# PowerManagementMysensors.net
KiCad netlist of a schematic drawn in EAGLE
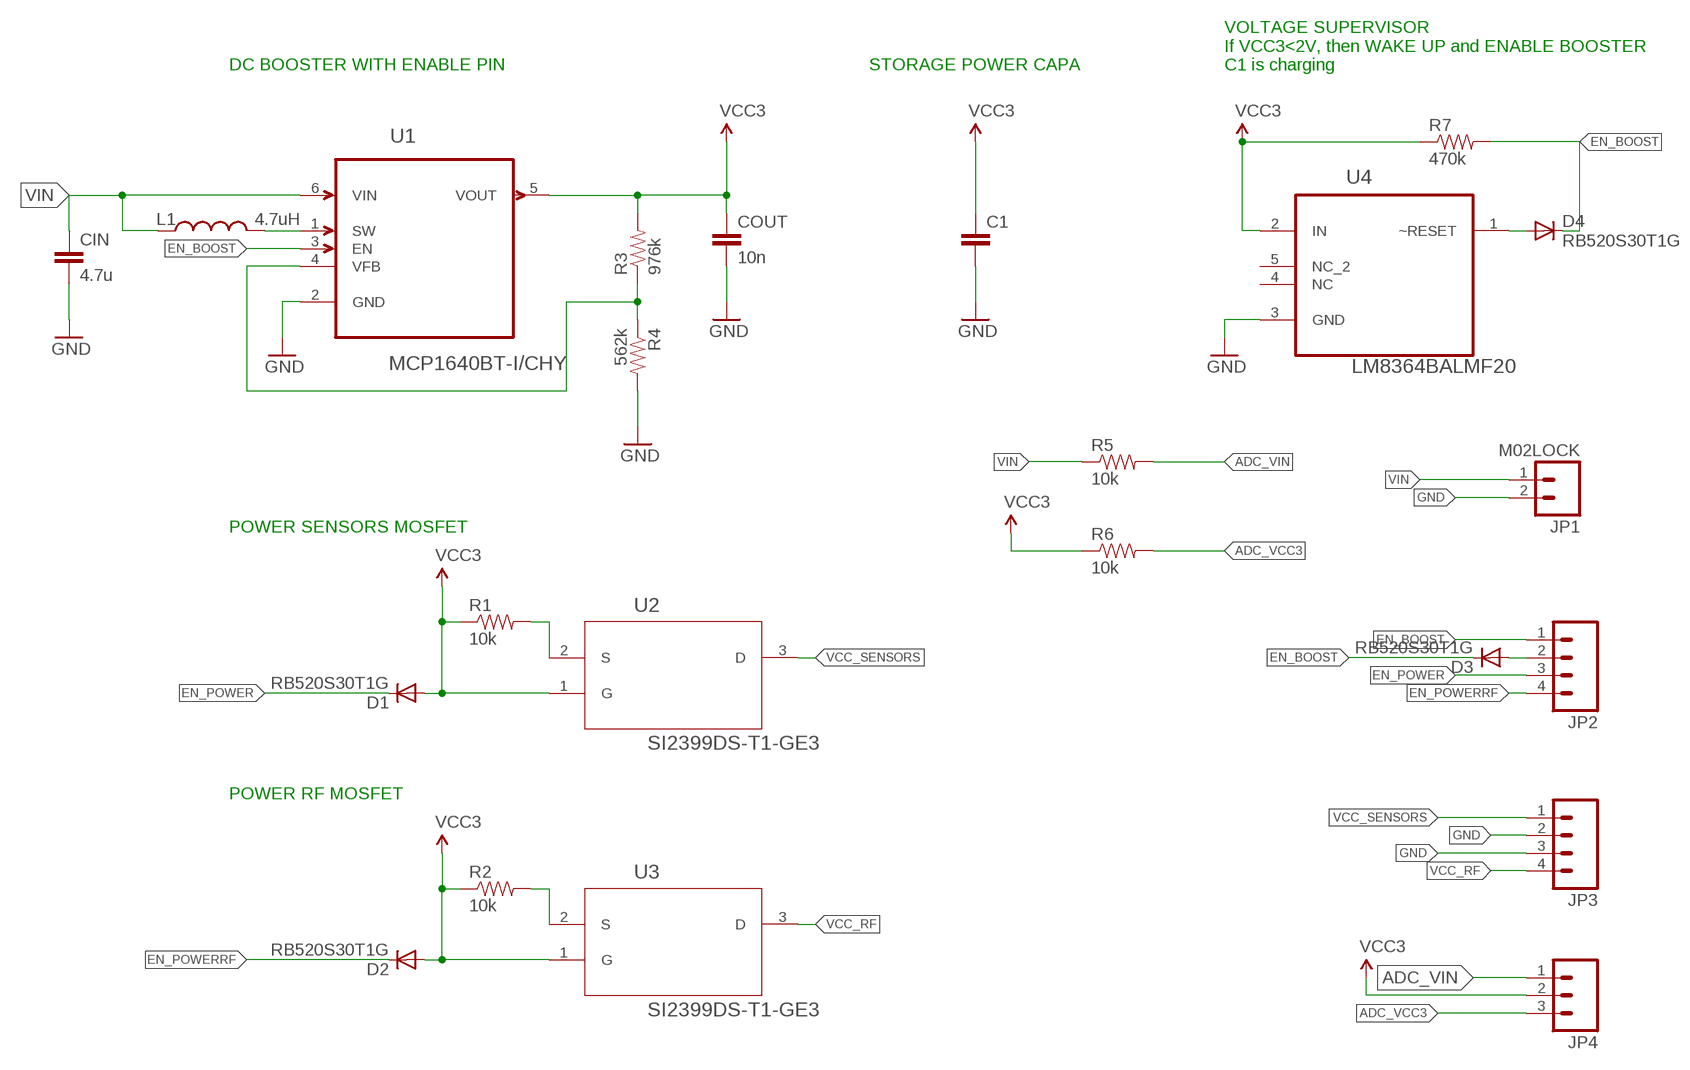
[diagram p0: schematic, sheet 1]

(export (version "E")
  (design (tool "Eeschema 10.0.6"))
  (components
    (comp (ref "C1")
      (value "CAP1206")
      (footprint "eagle-import:1206")
      (libsource (lib "eagle-import") (part "CAP1206"))
    )
    (comp (ref "CIN")
      (value "4.7u")
      (footprint "eagle-import:1206")
      (libsource (lib "eagle-import") (part "CAP1206"))
    )
    (comp (ref "COUT")
      (value "10n")
      (footprint "eagle-import:1206")
      (libsource (lib "eagle-import") (part "CAP1206"))
    )
    (comp (ref "D1")
      (value "RB520S30T1G")
      (footprint "eagle-import:SOD523")
      (libsource (lib "eagle-import") (part "DIODE-SOD523"))
    )
    (comp (ref "D2")
      (value "RB520S30T1G")
      (footprint "eagle-import:SOD523")
      (libsource (lib "eagle-import") (part "DIODE-SOD523"))
    )
    (comp (ref "D3")
      (value "RB520S30T1G")
      (footprint "eagle-import:SOD523")
      (libsource (lib "eagle-import") (part "DIODE-SOD523"))
    )
    (comp (ref "D4")
      (value "RB520S30T1G")
      (footprint "eagle-import:SOD523")
      (libsource (lib "eagle-import") (part "DIODE-SOD523"))
    )
    (comp (ref "JP1")
      (value "M02LOCK")
      (footprint "eagle-import:1X02_LOCK")
      (libsource (lib "eagle-import") (part "M02LOCK"))
    )
    (comp (ref "JP2")
      (value "M04LOCK")
      (footprint "eagle-import:1X04_LOCK")
      (libsource (lib "eagle-import") (part "M04LOCK"))
    )
    (comp (ref "JP3")
      (value "M041X04_NO_SILK")
      (footprint "eagle-import:1X04_NO_SILK")
      (libsource (lib "eagle-import") (part "M041X04_NO_SILK"))
    )
    (comp (ref "JP4")
      (value "M03LOCK")
      (footprint "eagle-import:1X03_LOCK")
      (libsource (lib "eagle-import") (part "M03LOCK"))
    )
    (comp (ref "L1")
      (value "4.7uH")
      (footprint "eagle-import:1210")
      (libsource (lib "eagle-import") (part "INDUCTOR1210"))
    )
    (comp (ref "R1")
      (value "10k")
      (footprint "eagle-import:1206")
      (libsource (lib "eagle-import") (part "RESISTOR1206"))
    )
    (comp (ref "R2")
      (value "10k")
      (footprint "eagle-import:1206")
      (libsource (lib "eagle-import") (part "RESISTOR1206"))
    )
    (comp (ref "R3")
      (value "976k")
      (footprint "eagle-import:1206")
      (libsource (lib "eagle-import") (part "RESISTOR1206"))
    )
    (comp (ref "R4")
      (value "562k")
      (footprint "eagle-import:1206")
      (libsource (lib "eagle-import") (part "RESISTOR1206"))
    )
    (comp (ref "R5")
      (value "10k")
      (footprint "eagle-import:1206")
      (libsource (lib "eagle-import") (part "RESISTOR1206"))
    )
    (comp (ref "R6")
      (value "10k")
      (footprint "eagle-import:1206")
      (libsource (lib "eagle-import") (part "RESISTOR1206"))
    )
    (comp (ref "R7")
      (value "470k")
      (footprint "eagle-import:1206")
      (libsource (lib "eagle-import") (part "RESISTOR1206"))
    )
    (comp (ref "U1")
      (value "MCP1640BT-I/CHY")
      (footprint "eagle-import:SOT95P270X145-6N")
      (libsource (lib "eagle-import") (part "MCP1640BT-I/CHY"))
    )
    (comp (ref "U2")
      (value "SI2399DS-T1-GE3")
      (footprint "eagle-import:SOT95P237X112-3N")
      (libsource (lib "eagle-import") (part "SI2399DS-T1-GE3"))
    )
    (comp (ref "U3")
      (value "SI2399DS-T1-GE3")
      (footprint "eagle-import:SOT95P237X112-3N")
      (libsource (lib "eagle-import") (part "SI2399DS-T1-GE3"))
    )
    (comp (ref "U4")
      (value "LM8364BALMF20")
      (footprint "eagle-import:SOT95P284X122-5N")
      (libsource (lib "eagle-import") (part "LM8364BALMF20"))
    )
  )
  (nets
    (net (code "1") (name "ADC_VCC3") (class "Default")
      (node (ref "JP4") (pin "3") (pinfunction "3_3") (pintype "passive"))
      (node (ref "R6") (pin "2") (pinfunction "2_2") (pintype "passive"))
    )
    (net (code "2") (name "ADC_VIN") (class "Default")
      (node (ref "JP4") (pin "1") (pinfunction "1_1") (pintype "passive"))
      (node (ref "R5") (pin "2") (pinfunction "2_2") (pintype "passive"))
    )
    (net (code "3") (name "EN_BOOST") (class "Default")
      (node (ref "D3") (pin "C") (pinfunction "C_C") (pintype "passive"))
      (node (ref "D4") (pin "C") (pinfunction "C_C") (pintype "passive"))
      (node (ref "JP2") (pin "1") (pinfunction "1_1") (pintype "passive"))
      (node (ref "R7") (pin "2") (pinfunction "2_2") (pintype "passive"))
      (node (ref "U1") (pin "3") (pinfunction "EN_3") (pintype "input"))
    )
    (net (code "4") (name "EN_POWER") (class "Default")
      (node (ref "D1") (pin "C") (pinfunction "C_C") (pintype "passive"))
      (node (ref "JP2") (pin "3") (pinfunction "3_3") (pintype "passive"))
    )
    (net (code "5") (name "EN_POWERRF") (class "Default")
      (node (ref "D2") (pin "C") (pinfunction "C_C") (pintype "passive"))
      (node (ref "JP2") (pin "4") (pinfunction "4_4") (pintype "passive"))
    )
    (net (code "6") (name "GND") (class "Default")
      (node (ref "C1") (pin "2") (pinfunction "2_2") (pintype "passive"))
      (node (ref "CIN") (pin "2") (pinfunction "2_2") (pintype "passive"))
      (node (ref "COUT") (pin "2") (pinfunction "2_2") (pintype "passive"))
      (node (ref "JP1") (pin "2") (pinfunction "2_2") (pintype "passive"))
      (node (ref "JP3") (pin "2") (pinfunction "2_2") (pintype "passive"))
      (node (ref "JP3") (pin "3") (pinfunction "3_3") (pintype "passive"))
      (node (ref "R4") (pin "2") (pinfunction "2_2") (pintype "passive"))
      (node (ref "U1") (pin "2") (pinfunction "GND_2") (pintype "passive"))
      (node (ref "U4") (pin "3") (pinfunction "GND_3") (pintype "passive"))
    )
    (net (code "7") (name "Net-(D3-PadA)") (class "Default")
      (node (ref "D3") (pin "A") (pinfunction "A_A") (pintype "passive"))
      (node (ref "JP2") (pin "2") (pinfunction "2_2") (pintype "passive"))
    )
    (net (code "8") (name "Net-(U1-SW)") (class "Default")
      (node (ref "L1") (pin "2") (pinfunction "2_2") (pintype "passive"))
      (node (ref "U1") (pin "1") (pinfunction "SW_1") (pintype "input"))
    )
    (net (code "9") (name "Net-(U1-VFB)") (class "Default")
      (node (ref "R3") (pin "1") (pinfunction "1_1") (pintype "passive"))
      (node (ref "R4") (pin "1") (pinfunction "1_1") (pintype "passive"))
      (node (ref "U1") (pin "4") (pinfunction "VFB_4") (pintype "input"))
    )
    (net (code "10") (name "Net-(U2-S)") (class "Default")
      (node (ref "R1") (pin "2") (pinfunction "2_2") (pintype "passive"))
      (node (ref "U2") (pin "2") (pinfunction "S_2") (pintype "passive"))
    )
    (net (code "11") (name "Net-(U3-S)") (class "Default")
      (node (ref "R2") (pin "2") (pinfunction "2_2") (pintype "passive"))
      (node (ref "U3") (pin "2") (pinfunction "S_2") (pintype "passive"))
    )
    (net (code "12") (name "Net-(U4-~{RESET})") (class "Default")
      (node (ref "D4") (pin "A") (pinfunction "A_A") (pintype "passive"))
      (node (ref "U4") (pin "1") (pinfunction "~{RESET}_1") (pintype "output"))
    )
    (net (code "13") (name "VCC3") (class "Default")
      (node (ref "C1") (pin "1") (pinfunction "1_1") (pintype "passive"))
      (node (ref "COUT") (pin "1") (pinfunction "1_1") (pintype "passive"))
      (node (ref "D1") (pin "A") (pinfunction "A_A") (pintype "passive"))
      (node (ref "D2") (pin "A") (pinfunction "A_A") (pintype "passive"))
      (node (ref "JP4") (pin "2") (pinfunction "2_2") (pintype "passive"))
      (node (ref "R1") (pin "1") (pinfunction "1_1") (pintype "passive"))
      (node (ref "R2") (pin "1") (pinfunction "1_1") (pintype "passive"))
      (node (ref "R3") (pin "2") (pinfunction "2_2") (pintype "passive"))
      (node (ref "R6") (pin "1") (pinfunction "1_1") (pintype "passive"))
      (node (ref "R7") (pin "1") (pinfunction "1_1") (pintype "passive"))
      (node (ref "U1") (pin "5") (pinfunction "VOUT_5") (pintype "output"))
      (node (ref "U2") (pin "1") (pinfunction "G_1") (pintype "passive"))
      (node (ref "U3") (pin "1") (pinfunction "G_1") (pintype "passive"))
      (node (ref "U4") (pin "2") (pinfunction "IN_2") (pintype "input"))
    )
    (net (code "14") (name "VCC_RF") (class "Default")
      (node (ref "JP3") (pin "4") (pinfunction "4_4") (pintype "passive"))
      (node (ref "U3") (pin "3") (pinfunction "D_3") (pintype "passive"))
    )
    (net (code "15") (name "VCC_SENSORS") (class "Default")
      (node (ref "JP3") (pin "1") (pinfunction "1_1") (pintype "passive"))
      (node (ref "U2") (pin "3") (pinfunction "D_3") (pintype "passive"))
    )
    (net (code "16") (name "VIN") (class "Default")
      (node (ref "CIN") (pin "1") (pinfunction "1_1") (pintype "passive"))
      (node (ref "JP1") (pin "1") (pinfunction "1_1") (pintype "passive"))
      (node (ref "L1") (pin "1") (pinfunction "1_1") (pintype "passive"))
      (node (ref "R5") (pin "1") (pinfunction "1_1") (pintype "passive"))
      (node (ref "U1") (pin "6") (pinfunction "VIN_6") (pintype "input"))
    )
    (net (code "17") (name "unconnected-(U4-NC-Pad4)") (class "Default")
      (node (ref "U4") (pin "4") (pinfunction "NC_4") (pintype "no_connect"))
    )
    (net (code "18") (name "unconnected-(U4-NC_2-Pad5)") (class "Default")
      (node (ref "U4") (pin "5") (pinfunction "NC_2_5") (pintype "no_connect"))
    )
  )
)
